# board.net
KiCad netlist of a schematic drawn in EAGLE
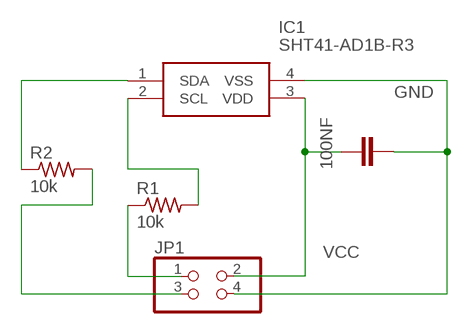
[diagram p0: schematic, sheet 1]

(export (version "E")
  (design (tool "Eeschema 10.0.6"))
  (components
    (comp (ref "100NF")
      (value "100nF")
      (footprint "eagle-import:CAP_0805")
      (fields
        (field (name "DIGIKEY_PART_NUMBER") "311-1140-2-ND")
        (field (name "MANUFACTURER") "Yageo")
        (field (name "MPN") "CC0805KRX7R9BB104")
        (field (name "CREATED_BY") "PCBLayout.com")
      )
      (libsource (lib "eagle-import") (part "CC0805KRX7R9BB104"))
    )
    (comp (ref "IC1")
      (value "SHT41-AD1B-R3")
      (footprint "eagle-import:SHT41AD1BR3")
      (fields (field (name "MOUSER_PART_NUMBER") "403-SHT41-AD1B-R3"))
      (libsource (lib "eagle-import") (part "SHT41-AD1B-R3"))
    )
    (comp (ref "JP1")
      (value "PINHD-2X2")
      (footprint "eagle-import:2X02")
      (libsource (lib "eagle-import") (part "PINHD-2X2"))
    )
    (comp (ref "R1")
      (value "10k")
      (footprint "eagle-import:RES_0805")
      (fields
        (field (name "DIGIKEY_PART_NUMBER") "541-0.0ATR-ND")
        (field (name "MANUFACTURER") "Vishay Dale")
        (field (name "MPN") "CRCW08050000Z0EA")
        (field (name "CREATED_BY") "PCBLayout.com")
      )
      (libsource (lib "eagle-import") (part "CRCW08050000Z0EA"))
    )
    (comp (ref "R2")
      (value "10k")
      (footprint "eagle-import:RES_0805")
      (fields
        (field (name "DIGIKEY_PART_NUMBER") "541-0.0ATR-ND")
        (field (name "MANUFACTURER") "Vishay Dale")
        (field (name "MPN") "CRCW08050000Z0EA")
        (field (name "CREATED_BY") "PCBLayout.com")
      )
      (libsource (lib "eagle-import") (part "CRCW08050000Z0EA"))
    )
  )
  (nets
    (net (code "1") (name "/GND") (class "Default")
      (node (ref "100NF") (pin "2") (pinfunction "2_2") (pintype "passive"))
      (node (ref "IC1") (pin "4") (pinfunction "VSS_4") (pintype "bidirectional"))
      (node (ref "JP1") (pin "4") (pinfunction "4_4") (pintype "passive"))
    )
    (net (code "2") (name "/VCC") (class "Default")
      (node (ref "100NF") (pin "1") (pinfunction "1_1") (pintype "passive"))
      (node (ref "IC1") (pin "3") (pinfunction "VDD_3") (pintype "bidirectional"))
      (node (ref "JP1") (pin "2") (pinfunction "2_2") (pintype "passive"))
    )
    (net (code "3") (name "Net-(IC1-SCL)") (class "Default")
      (node (ref "IC1") (pin "2") (pinfunction "SCL_2") (pintype "bidirectional"))
      (node (ref "R1") (pin "2") (pinfunction "2_2") (pintype "passive"))
    )
    (net (code "4") (name "Net-(IC1-SDA)") (class "Default")
      (node (ref "IC1") (pin "1") (pinfunction "SDA_1") (pintype "bidirectional"))
      (node (ref "R2") (pin "1") (pinfunction "1_1") (pintype "passive"))
    )
    (net (code "5") (name "Net-(JP1-Pad1)") (class "Default")
      (node (ref "JP1") (pin "1") (pinfunction "1_1") (pintype "passive"))
      (node (ref "R1") (pin "1") (pinfunction "1_1") (pintype "passive"))
    )
    (net (code "6") (name "Net-(JP1-Pad3)") (class "Default")
      (node (ref "JP1") (pin "3") (pinfunction "3_3") (pintype "passive"))
      (node (ref "R2") (pin "2") (pinfunction "2_2") (pintype "passive"))
    )
  )
)
